# neopixel-6-display-controller.net
KiCad netlist of a schematic drawn in EasyEDA Pro
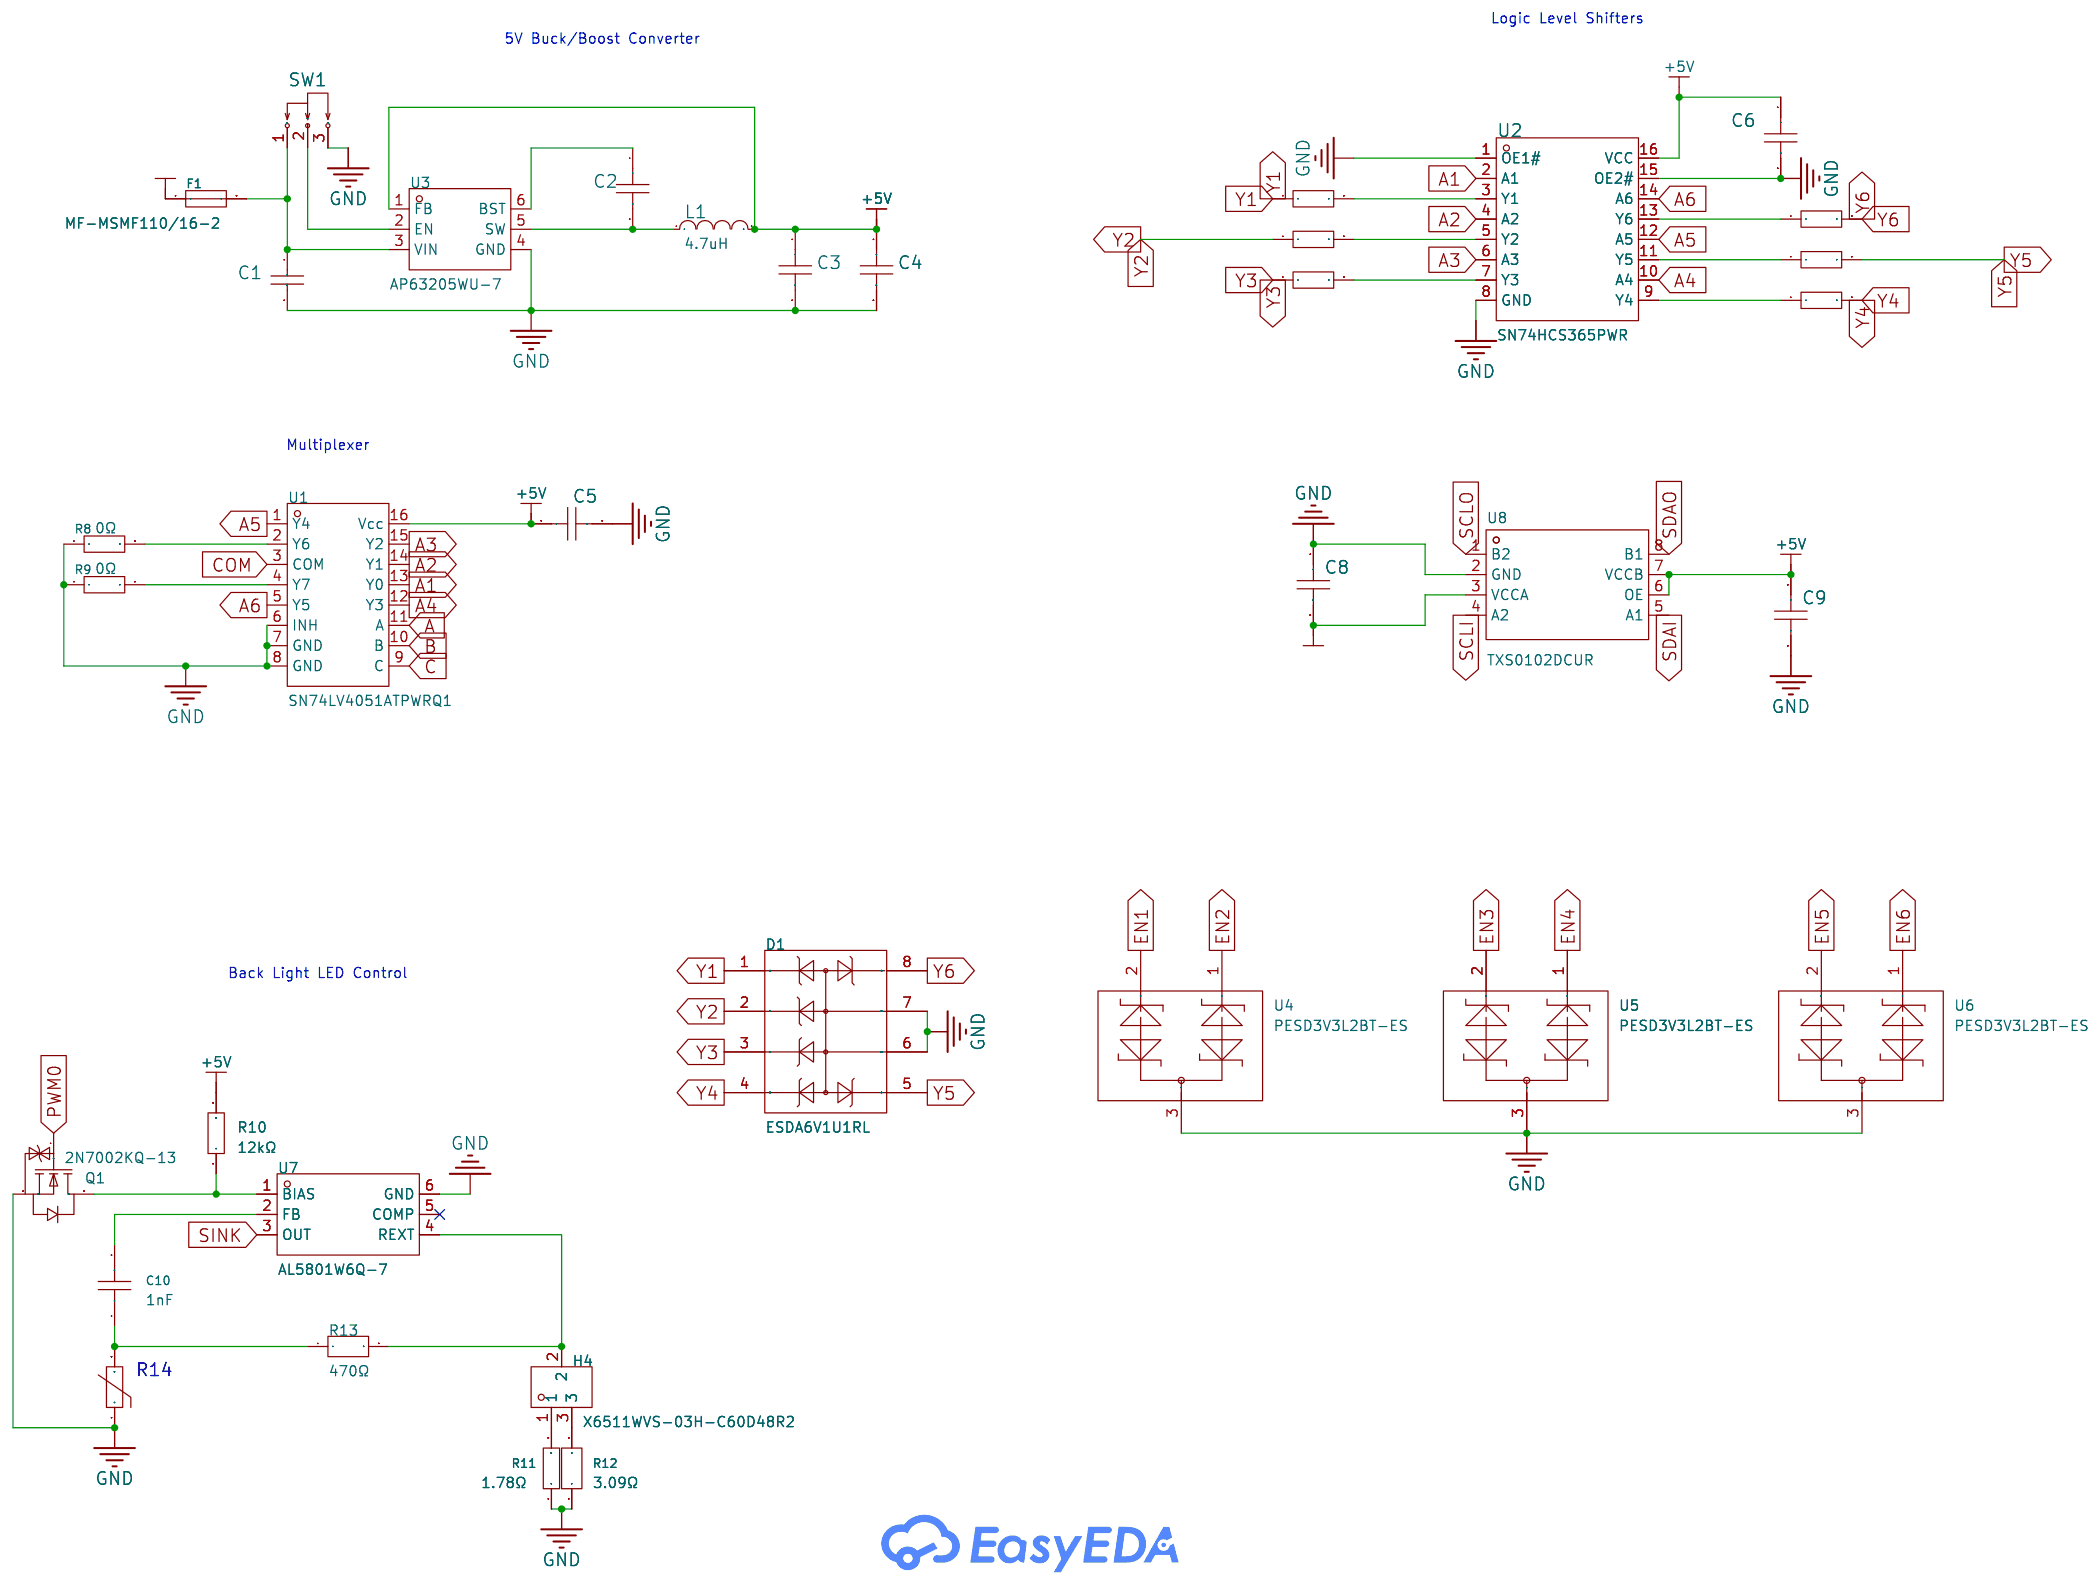
[diagram p0: Components]
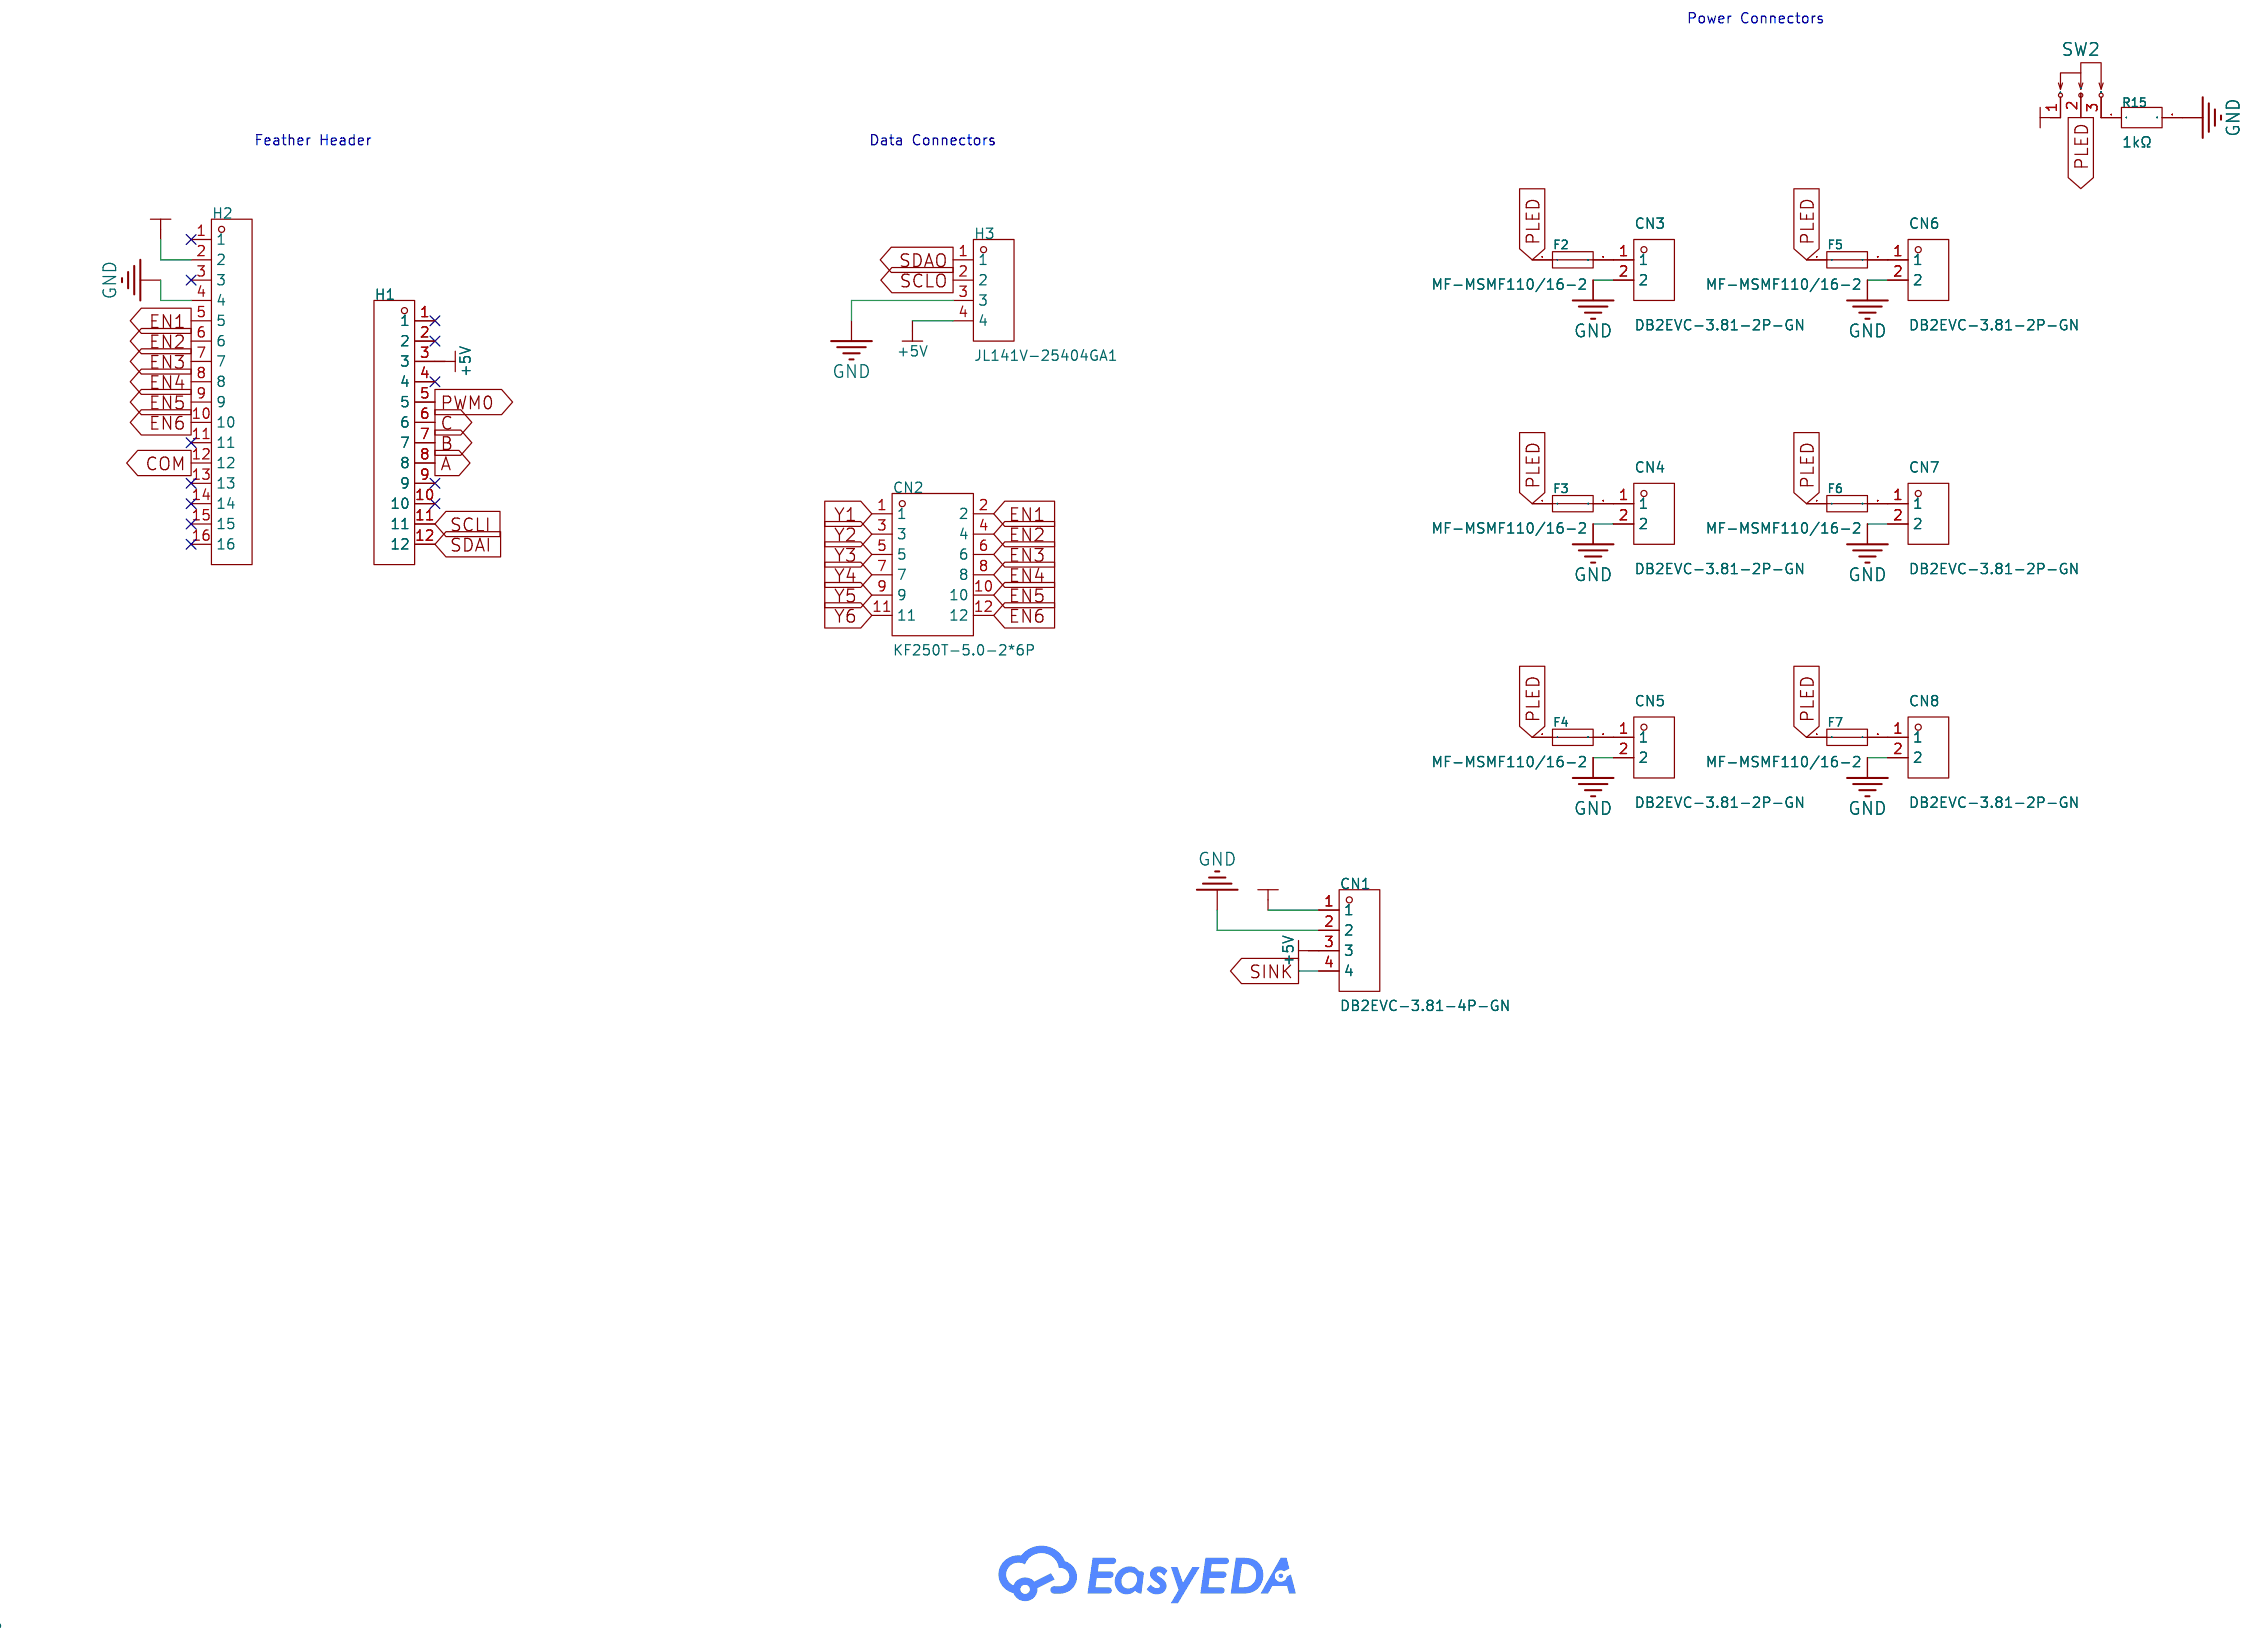
[diagram p1: Connectors]

(export (version "E")
  (design (tool "Eeschema 10.0.6"))
  (components
    (comp (ref "C1")
      (value "10uF")
      (footprint "easyedapro:C1210")
      (fields
        (field (name "Manufacturer Part") "CL32B106KAJNNNE")
        (field (name "Manufacturer") "SAMSUNG(三星)")
      )
      (libsource (lib "easyedapro") (part "CL32B106KAJNNNE"))
    )
    (comp (ref "C2")
      (value "100nF")
      (footprint "easyedapro:C1206")
      (fields (field (name "Manufacturer Part") "1206N104J500CT") (field (name "Manufacturer") "Walsin(华新科)"))
      (libsource (lib "easyedapro") (part "1206N104J500"))
    )
    (comp (ref "C3")
      (value "22uF")
      (footprint "easyedapro:C1210")
      (fields
        (field (name "Manufacturer Part") "CL32B226KAJNNNE")
        (field (name "Manufacturer") "SAMSUNG(三星)")
      )
      (libsource (lib "easyedapro") (part "CL32B226KAJNNNE"))
    )
    (comp (ref "C4")
      (value "22uF")
      (footprint "easyedapro:C1210")
      (fields
        (field (name "Manufacturer Part") "CL32B226KAJNNNE")
        (field (name "Manufacturer") "SAMSUNG(三星)")
      )
      (libsource (lib "easyedapro") (part "CL32B226KAJNNNE"))
    )
    (comp (ref "C5")
      (value "100nF")
      (footprint "easyedapro:C1206")
      (fields (field (name "Manufacturer Part") "1206N104J500CT") (field (name "Manufacturer") "Walsin(华新科)"))
      (libsource (lib "easyedapro") (part "1206N104J500"))
    )
    (comp (ref "C6")
      (value "100nF")
      (footprint "easyedapro:C1206")
      (fields (field (name "Manufacturer Part") "1206N104J500CT") (field (name "Manufacturer") "Walsin(华新科)"))
      (libsource (lib "easyedapro") (part "1206N104J500"))
    )
    (comp (ref "C8")
      (value "100nF")
      (footprint "easyedapro:C1206")
      (fields (field (name "Manufacturer Part") "1206N104J500CT") (field (name "Manufacturer") "Walsin(华新科)"))
      (libsource (lib "easyedapro") (part "1206N104J500"))
    )
    (comp (ref "C9")
      (value "100nF")
      (footprint "easyedapro:C1206")
      (fields (field (name "Manufacturer Part") "1206N104J500CT") (field (name "Manufacturer") "Walsin(华新科)"))
      (libsource (lib "easyedapro") (part "1206N104J500"))
    )
    (comp (ref "C10")
      (value "1nF")
      (footprint "easyedapro:C0402")
      (fields
        (field (name "Manufacturer Part") "GRM1555C1H102JA01D")
        (field (name "Manufacturer") "muRata(村田)")
      )
      (libsource (lib "easyedapro") (part "GRM1555C1H102JA01D"))
    )
    (comp (ref "D1")
      (value "ESDA6V1U1RL")
      (footprint "easyedapro:SO-8_L4.9-W3.9-P1.27-LS5.9-BL")
      (fields (field (name "Manufacturer") "ST(意法半导体)"))
      (libsource (lib "easyedapro") (part "ESDA6V1U1RL"))
    )
    (comp (ref "F1")
      (value "MF-MSMF110/16-2")
      (footprint "easyedapro:F1812")
      (fields (field (name "Manufacturer") "BOURNS"))
      (libsource (lib "easyedapro") (part "MF-MSMF110/16-2"))
    )
    (comp (ref "H4")
      (value "X6511WVS-03H-C60D48R2")
      (footprint "easyedapro:HDR-SMD_3P-P2.54_XKB_X6511WVS-03H-C60D48R2")
      (fields (field (name "Manufacturer") "XKB Connection(中国星坤)"))
      (libsource (lib "easyedapro") (part "X6511WVS-03H-C60D48R2"))
    )
    (comp (ref "L1")
      (value "4.7uH")
      (footprint "easyedapro:IND-SMD_L7.0-W7.0_CDRR7D45T125NP")
      (fields
        (field (name "Manufacturer Part") "CDRR7D45T125NP-4R7MC")
        (field (name "Manufacturer") "Sumida(胜美达)")
      )
      (libsource (lib "easyedapro") (part "CDRR7D45T125NP-4R7MC"))
    )
    (comp (ref "Q1")
      (value "2N7002KQ-13")
      (footprint "easyedapro:SOT-23-3_L2.9-W1.3-P1.90-LS2.4-BR")
      (fields (field (name "Manufacturer") "DIODES(美台)"))
      (libsource (lib "easyedapro") (part "2N7002KQ-13"))
    )
    (comp (ref "R1")
      (value "100Ω")
      (footprint "easyedapro:R0805")
      (fields (field (name "Manufacturer Part") "ERA6AEB101V") (field (name "Manufacturer") "PANASONIC(松下)"))
      (libsource (lib "easyedapro") (part "ERA6AEB101V"))
    )
    (comp (ref "R2")
      (value "100Ω")
      (footprint "easyedapro:R0805")
      (fields (field (name "Manufacturer Part") "ERA6AEB101V") (field (name "Manufacturer") "PANASONIC(松下)"))
      (libsource (lib "easyedapro") (part "ERA6AEB101V"))
    )
    (comp (ref "R3")
      (value "100Ω")
      (footprint "easyedapro:R0805")
      (fields (field (name "Manufacturer Part") "ERA6AEB101V") (field (name "Manufacturer") "PANASONIC(松下)"))
      (libsource (lib "easyedapro") (part "ERA6AEB101V"))
    )
    (comp (ref "R4")
      (value "100Ω")
      (footprint "easyedapro:R0805")
      (fields (field (name "Manufacturer Part") "ERA6AEB101V") (field (name "Manufacturer") "PANASONIC(松下)"))
      (libsource (lib "easyedapro") (part "ERA6AEB101V"))
    )
    (comp (ref "R5")
      (value "100Ω")
      (footprint "easyedapro:R0805")
      (fields (field (name "Manufacturer Part") "ERA6AEB101V") (field (name "Manufacturer") "PANASONIC(松下)"))
      (libsource (lib "easyedapro") (part "ERA6AEB101V"))
    )
    (comp (ref "R6")
      (value "100Ω")
      (footprint "easyedapro:R0805")
      (fields (field (name "Manufacturer Part") "ERA6AEB101V") (field (name "Manufacturer") "PANASONIC(松下)"))
      (libsource (lib "easyedapro") (part "ERA6AEB101V"))
    )
    (comp (ref "R8")
      (value "0Ω")
      (footprint "easyedapro:R0805")
      (fields (field (name "Manufacturer Part") "RTT050000FTP") (field (name "Manufacturer") "RALEC(旺诠)"))
      (libsource (lib "easyedapro") (part "RTT050000FTP"))
    )
    (comp (ref "R9")
      (value "0Ω")
      (footprint "easyedapro:R0805")
      (fields (field (name "Manufacturer Part") "RTT050000FTP") (field (name "Manufacturer") "RALEC(旺诠)"))
      (libsource (lib "easyedapro") (part "RTT050000FTP"))
    )
    (comp (ref "R10")
      (value "12kΩ")
      (footprint "easyedapro:R0805")
      (fields (field (name "Manufacturer Part") "PTFR0805B12K0N9") (field (name "Manufacturer") "RESI(开步睿思)"))
      (libsource (lib "easyedapro") (part "PTFR0805B12K0N9"))
    )
    (comp (ref "R11")
      (value "1.78Ω")
      (footprint "easyedapro:R0805")
      (fields
        (field (name "Manufacturer Part") "TR0805D1R78P0525")
        (field (name "Manufacturer") "EVER OHMS(天二科技)")
      )
      (libsource (lib "easyedapro") (part "TR0805D1R78P0525"))
    )
    (comp (ref "R12")
      (value "3.09Ω")
      (footprint "easyedapro:R0805")
      (fields (field (name "Manufacturer Part") "WR08W3R09FTL") (field (name "Manufacturer") "Walsin(华新科)"))
      (libsource (lib "easyedapro") (part "WR08W3R09FTL"))
    )
    (comp (ref "R13")
      (value "470Ω")
      (footprint "easyedapro:R0402")
      (fields (field (name "Manufacturer Part") "ERA2AEB471X") (field (name "Manufacturer") "PANASONIC(松下)"))
      (libsource (lib "easyedapro") (part "ERA2AEB471X"))
    )
    (comp (ref "R14")
      (value "10k")
      (footprint "easyedapro:R0805")
      (fields
        (field (name "Manufacturer Part") "KNTC0805/10KJ3450")
        (field (name "Manufacturer") "KUU")
        (field (name "Tolerance") "±0.5%")
      )
      (libsource (lib "easyedapro") (part "KNTC0805/10KJ3450"))
    )
    (comp (ref "SW1")
      (value "SS12D10G4 071")
      (footprint "easyedapro:SW-TH_SHOU-HAN_SS12D10G4")
      (fields (field (name "Manufacturer") "SHOU HAN(首韩)"))
      (libsource (lib "easyedapro") (part "SS12D10G4 071"))
    )
    (comp (ref "U1")
      (value "SN74LV4051ATPWRQ1")
      (footprint "easyedapro:TSSOP-16_L5.0-W4.4-P0.65-LS6.4-BL")
      (fields (field (name "Manufacturer") "TI(德州仪器)"))
      (libsource (lib "easyedapro") (part "SN74LV4051ATPWRQ1"))
    )
    (comp (ref "U2")
      (value "SN74HCS365PWR")
      (footprint "easyedapro:TSSOP-16_L5.0-W4.4-P0.65-LS6.4-BL")
      (fields (field (name "Manufacturer") "TI(德州仪器)"))
      (libsource (lib "easyedapro") (part "SN74HCS365PWR"))
    )
    (comp (ref "U3")
      (value "AP63205WU-7")
      (footprint "easyedapro:TSOT-23-6_L2.9-W1.6-P0.95-LS2.8-BL")
      (fields (field (name "Manufacturer") "DIODES(美台)"))
      (libsource (lib "easyedapro") (part "AP63205WU-7"))
    )
    (comp (ref "U4")
      (value "PESD3V3L2BT-ES")
      (footprint "easyedapro:SOT-23-3_L2.9-W1.3-P0.95-LS2.4-BR")
      (fields (field (name "Manufacturer") "ElecSuper(静芯微)"))
      (libsource (lib "easyedapro") (part "PESD3V3L2BT-ES"))
    )
    (comp (ref "U5")
      (value "PESD3V3L2BT-ES")
      (footprint "easyedapro:SOT-23-3_L2.9-W1.3-P0.95-LS2.4-BR")
      (fields (field (name "Manufacturer") "ElecSuper(静芯微)"))
      (libsource (lib "easyedapro") (part "PESD3V3L2BT-ES"))
    )
    (comp (ref "U6")
      (value "PESD3V3L2BT-ES")
      (footprint "easyedapro:SOT-23-3_L2.9-W1.3-P0.95-LS2.4-BR")
      (fields (field (name "Manufacturer") "ElecSuper(静芯微)"))
      (libsource (lib "easyedapro") (part "PESD3V3L2BT-ES"))
    )
    (comp (ref "U7")
      (value "AL5801W6Q-7")
      (footprint "easyedapro:SOT-26-6_L3.0-W1.6-P0.95-LS2.8-BL")
      (fields (field (name "Manufacturer") "DIODES(美台)"))
      (libsource (lib "easyedapro") (part "AL5801W6Q-7"))
    )
    (comp (ref "U8")
      (value "TXS0102DCUR")
      (footprint "easyedapro:VSON8_L2.0-W2.3-P0.50-LS3.1-BL")
      (fields (field (name "Manufacturer") "TI(德州仪器)"))
      (libsource (lib "easyedapro") (part "TXS0102DCUR"))
    )
    (comp (ref "CN1")
      (value "DB2EVC-3.81-4P-GN")
      (footprint "easyedapro:CONN-TH_4P-P3.81_DB2EVC-3.81-4P")
      (fields (field (name "Manufacturer") "DORABO(地博电气)"))
      (libsource (lib "easyedapro") (part "DB2EVC-3.81-4P"))
    )
    (comp (ref "CN2")
      (value "KF250T-5.0-2*6P")
      (footprint "easyedapro:CONN-TH_KF250T-5.0-2X6P")
      (fields (field (name "Manufacturer") "KEFA(科发)"))
      (libsource (lib "easyedapro") (part "KF250T-5.0-2*6P"))
    )
    (comp (ref "CN3")
      (value "DB2EVC-3.81-2P-GN")
      (footprint "easyedapro:CONN-TH_2P-P3.81_DB2EVC-3.81-2P-BK")
      (fields (field (name "Manufacturer") "DORABO(地博电气)"))
      (libsource (lib "easyedapro") (part "DB2EVC-3.81-2P"))
    )
    (comp (ref "CN4")
      (value "DB2EVC-3.81-2P-GN")
      (footprint "easyedapro:CONN-TH_2P-P3.81_DB2EVC-3.81-2P-BK")
      (fields (field (name "Manufacturer") "DORABO(地博电气)"))
      (libsource (lib "easyedapro") (part "DB2EVC-3.81-2P"))
    )
    (comp (ref "CN5")
      (value "DB2EVC-3.81-2P-GN")
      (footprint "easyedapro:CONN-TH_2P-P3.81_DB2EVC-3.81-2P-BK")
      (fields (field (name "Manufacturer") "DORABO(地博电气)"))
      (libsource (lib "easyedapro") (part "DB2EVC-3.81-2P"))
    )
    (comp (ref "CN6")
      (value "DB2EVC-3.81-2P-GN")
      (footprint "easyedapro:CONN-TH_2P-P3.81_DB2EVC-3.81-2P-BK")
      (fields (field (name "Manufacturer") "DORABO(地博电气)"))
      (libsource (lib "easyedapro") (part "DB2EVC-3.81-2P"))
    )
    (comp (ref "CN7")
      (value "DB2EVC-3.81-2P-GN")
      (footprint "easyedapro:CONN-TH_2P-P3.81_DB2EVC-3.81-2P-BK")
      (fields (field (name "Manufacturer") "DORABO(地博电气)"))
      (libsource (lib "easyedapro") (part "DB2EVC-3.81-2P"))
    )
    (comp (ref "CN8")
      (value "DB2EVC-3.81-2P-GN")
      (footprint "easyedapro:CONN-TH_2P-P3.81_DB2EVC-3.81-2P-BK")
      (fields (field (name "Manufacturer") "DORABO(地博电气)"))
      (libsource (lib "easyedapro") (part "DB2EVC-3.81-2P"))
    )
    (comp (ref "F2")
      (value "MF-MSMF110/16-2")
      (footprint "easyedapro:F1812")
      (fields (field (name "Manufacturer") "BOURNS"))
      (libsource (lib "easyedapro") (part "MF-MSMF110/16-2"))
    )
    (comp (ref "F3")
      (value "MF-MSMF110/16-2")
      (footprint "easyedapro:F1812")
      (fields (field (name "Manufacturer") "BOURNS"))
      (libsource (lib "easyedapro") (part "MF-MSMF110/16-2"))
    )
    (comp (ref "F4")
      (value "MF-MSMF110/16-2")
      (footprint "easyedapro:F1812")
      (fields (field (name "Manufacturer") "BOURNS"))
      (libsource (lib "easyedapro") (part "MF-MSMF110/16-2"))
    )
    (comp (ref "F5")
      (value "MF-MSMF110/16-2")
      (footprint "easyedapro:F1812")
      (fields (field (name "Manufacturer") "BOURNS"))
      (libsource (lib "easyedapro") (part "MF-MSMF110/16-2"))
    )
    (comp (ref "F6")
      (value "MF-MSMF110/16-2")
      (footprint "easyedapro:F1812")
      (fields (field (name "Manufacturer") "BOURNS"))
      (libsource (lib "easyedapro") (part "MF-MSMF110/16-2"))
    )
    (comp (ref "F7")
      (value "MF-MSMF110/16-2")
      (footprint "easyedapro:F1812")
      (fields (field (name "Manufacturer") "BOURNS"))
      (libsource (lib "easyedapro") (part "MF-MSMF110/16-2"))
    )
    (comp (ref "H1")
      (value "A2541HWV-12P")
      (footprint "easyedapro:HDR-TH_12P-P2.54-V-F")
      (fields (field (name "Manufacturer") "CJT(长江连接器)"))
      (libsource (lib "easyedapro") (part "PM2.54-1*12"))
    )
    (comp (ref "H2")
      (value "ZX-PM2.54-1-16PY")
      (footprint "easyedapro:HDR-TH_16P-P2.54-V-F-A")
      (fields (field (name "Manufacturer") "Megastar(兆星)"))
      (libsource (lib "easyedapro") (part "PM254-1-16-Z-8.5"))
    )
    (comp (ref "H3")
      (value "JL141V-25404GA1")
      (footprint "easyedapro:CONN-TH_4P-P2.54_JILN_JL141V-25404GA1")
      (fields (field (name "Manufacturer") "JILN(锦凌)"))
      (libsource (lib "easyedapro") (part "JL141V-25404GA1"))
    )
    (comp (ref "R15")
      (value "1kΩ")
      (footprint "easyedapro:R0805")
      (fields
        (field (name "Manufacturer Part") "ERJ-HP6F1001V")
        (field (name "Manufacturer") "PANASONIC(松下)")
      )
      (libsource (lib "easyedapro") (part "ERJ-HP6F1001V"))
    )
    (comp (ref "SW2")
      (value "SS12D10G4 071")
      (footprint "easyedapro:SW-TH_SHOU-HAN_SS12D10G4")
      (fields (field (name "Manufacturer") "SHOU HAN(首韩)"))
      (libsource (lib "easyedapro") (part "SS12D10G4 071"))
    )
  )
  (nets
    (net (code "1") (name "+3.3V") (class "Default")
      (node (ref "C8") (pin "2") (pinfunction "2_2") (pintype "unspecified"))
      (node (ref "H2") (pin "2") (pinfunction "2_2") (pintype "unspecified"))
      (node (ref "U8") (pin "3") (pinfunction "VCCA_3") (pintype "unspecified"))
    )
    (net (code "2") (name "+5V") (class "Default")
      (node (ref "C3") (pin "1") (pinfunction "1_1") (pintype "unspecified"))
      (node (ref "C4") (pin "1") (pinfunction "1_1") (pintype "unspecified"))
      (node (ref "C5") (pin "1") (pinfunction "1_1") (pintype "unspecified"))
      (node (ref "C6") (pin "1") (pinfunction "1_1") (pintype "unspecified"))
      (node (ref "C9") (pin "1") (pinfunction "1_1") (pintype "unspecified"))
      (node (ref "CN1") (pin "3") (pinfunction "3_3") (pintype "unspecified"))
      (node (ref "H1") (pin "3") (pinfunction "3_3") (pintype "unspecified"))
      (node (ref "H3") (pin "4") (pinfunction "4_4") (pintype "unspecified"))
      (node (ref "L1") (pin "2") (pinfunction "2_2") (pintype "input"))
      (node (ref "R10") (pin "2") (pinfunction "2_2") (pintype "unspecified"))
      (node (ref "U1") (pin "16") (pinfunction "Vcc_16") (pintype "unspecified"))
      (node (ref "U2") (pin "16") (pinfunction "VCC_16") (pintype "input"))
      (node (ref "U3") (pin "1") (pinfunction "FB_1") (pintype "input"))
      (node (ref "U8") (pin "6") (pinfunction "OE_6") (pintype "unspecified"))
      (node (ref "U8") (pin "7") (pinfunction "VCCB_7") (pintype "unspecified"))
    )
    (net (code "3") (name "A") (class "Default")
      (node (ref "H1") (pin "8") (pinfunction "8_8") (pintype "unspecified"))
      (node (ref "U1") (pin "11") (pinfunction "A_11") (pintype "unspecified"))
    )
    (net (code "4") (name "A1") (class "Default")
      (node (ref "U1") (pin "13") (pinfunction "Y0_13") (pintype "unspecified"))
      (node (ref "U2") (pin "2") (pinfunction "A1_2") (pintype "input"))
    )
    (net (code "5") (name "A2") (class "Default")
      (node (ref "U1") (pin "14") (pinfunction "Y1_14") (pintype "unspecified"))
      (node (ref "U2") (pin "4") (pinfunction "A2_4") (pintype "input"))
    )
    (net (code "6") (name "A3") (class "Default")
      (node (ref "U1") (pin "15") (pinfunction "Y2_15") (pintype "unspecified"))
      (node (ref "U2") (pin "6") (pinfunction "A3_6") (pintype "input"))
    )
    (net (code "7") (name "A4") (class "Default")
      (node (ref "U1") (pin "12") (pinfunction "Y3_12") (pintype "unspecified"))
      (node (ref "U2") (pin "10") (pinfunction "A4_10") (pintype "input"))
    )
    (net (code "8") (name "A5") (class "Default")
      (node (ref "U1") (pin "1") (pinfunction "Y4_1") (pintype "unspecified"))
      (node (ref "U2") (pin "12") (pinfunction "A5_12") (pintype "input"))
    )
    (net (code "9") (name "A6") (class "Default")
      (node (ref "U1") (pin "5") (pinfunction "Y5_5") (pintype "unspecified"))
      (node (ref "U2") (pin "14") (pinfunction "A6_14") (pintype "input"))
    )
    (net (code "10") (name "B") (class "Default")
      (node (ref "H1") (pin "7") (pinfunction "7_7") (pintype "unspecified"))
      (node (ref "U1") (pin "10") (pinfunction "B_10") (pintype "unspecified"))
    )
    (net (code "11") (name "C") (class "Default")
      (node (ref "H1") (pin "6") (pinfunction "6_6") (pintype "unspecified"))
      (node (ref "U1") (pin "9") (pinfunction "C_9") (pintype "unspecified"))
    )
    (net (code "12") (name "COM") (class "Default")
      (node (ref "H2") (pin "12") (pinfunction "12_12") (pintype "unspecified"))
      (node (ref "U1") (pin "3") (pinfunction "COM_3") (pintype "unspecified"))
    )
    (net (code "13") (name "EN1") (class "Default")
      (node (ref "CN2") (pin "2") (pinfunction "2_2") (pintype "unspecified"))
      (node (ref "H2") (pin "5") (pinfunction "5_5") (pintype "unspecified"))
      (node (ref "U4") (pin "2") (pinfunction "2_2") (pintype "input"))
    )
    (net (code "14") (name "EN2") (class "Default")
      (node (ref "CN2") (pin "4") (pinfunction "4_4") (pintype "unspecified"))
      (node (ref "H2") (pin "6") (pinfunction "6_6") (pintype "unspecified"))
      (node (ref "U4") (pin "1") (pinfunction "1_1") (pintype "input"))
    )
    (net (code "15") (name "EN3") (class "Default")
      (node (ref "CN2") (pin "6") (pinfunction "6_6") (pintype "unspecified"))
      (node (ref "H2") (pin "7") (pinfunction "7_7") (pintype "unspecified"))
      (node (ref "U5") (pin "2") (pinfunction "2_2") (pintype "input"))
    )
    (net (code "16") (name "EN4") (class "Default")
      (node (ref "CN2") (pin "8") (pinfunction "8_8") (pintype "unspecified"))
      (node (ref "H2") (pin "8") (pinfunction "8_8") (pintype "unspecified"))
      (node (ref "U5") (pin "1") (pinfunction "1_1") (pintype "input"))
    )
    (net (code "17") (name "EN5") (class "Default")
      (node (ref "CN2") (pin "10") (pinfunction "10_10") (pintype "unspecified"))
      (node (ref "H2") (pin "9") (pinfunction "9_9") (pintype "unspecified"))
      (node (ref "U6") (pin "2") (pinfunction "2_2") (pintype "input"))
    )
    (net (code "18") (name "EN6") (class "Default")
      (node (ref "CN2") (pin "12") (pinfunction "12_12") (pintype "unspecified"))
      (node (ref "H2") (pin "10") (pinfunction "10_10") (pintype "unspecified"))
      (node (ref "U6") (pin "1") (pinfunction "1_1") (pintype "input"))
    )
    (net (code "19") (name "GND") (class "Default")
      (node (ref "C1") (pin "2") (pinfunction "2_2") (pintype "input"))
      (node (ref "C3") (pin "2") (pinfunction "2_2") (pintype "unspecified"))
      (node (ref "C4") (pin "2") (pinfunction "2_2") (pintype "unspecified"))
      (node (ref "C5") (pin "2") (pinfunction "2_2") (pintype "unspecified"))
      (node (ref "C6") (pin "2") (pinfunction "2_2") (pintype "unspecified"))
      (node (ref "C8") (pin "1") (pinfunction "1_1") (pintype "unspecified"))
      (node (ref "C9") (pin "2") (pinfunction "2_2") (pintype "unspecified"))
      (node (ref "CN1") (pin "2") (pinfunction "2_2") (pintype "unspecified"))
      (node (ref "CN3") (pin "2") (pinfunction "2_2") (pintype "unspecified"))
      (node (ref "CN4") (pin "2") (pinfunction "2_2") (pintype "unspecified"))
      (node (ref "CN5") (pin "2") (pinfunction "2_2") (pintype "unspecified"))
      (node (ref "CN6") (pin "2") (pinfunction "2_2") (pintype "unspecified"))
      (node (ref "CN7") (pin "2") (pinfunction "2_2") (pintype "unspecified"))
      (node (ref "CN8") (pin "2") (pinfunction "2_2") (pintype "unspecified"))
      (node (ref "D1") (pin "6") (pinfunction "GND_6") (pintype "unspecified"))
      (node (ref "D1") (pin "7") (pinfunction "GND_7") (pintype "unspecified"))
      (node (ref "H2") (pin "4") (pinfunction "4_4") (pintype "unspecified"))
      (node (ref "H3") (pin "3") (pinfunction "3_3") (pintype "unspecified"))
      (node (ref "Q1") (pin "2") (pinfunction "S_2") (pintype "unspecified"))
      (node (ref "R11") (pin "1") (pinfunction "1_1") (pintype "input"))
      (node (ref "R12") (pin "1") (pinfunction "1_1") (pintype "input"))
      (node (ref "R14") (pin "1") (pinfunction "1_1") (pintype "unspecified"))
      (node (ref "R15") (pin "2") (pinfunction "2_2") (pintype "input"))
      (node (ref "R8") (pin "1") (pinfunction "1_1") (pintype "input"))
      (node (ref "R9") (pin "1") (pinfunction "1_1") (pintype "input"))
      (node (ref "SW1") (pin "3") (pinfunction "3_3") (pintype "input"))
      (node (ref "U1") (pin "6") (pinfunction "INH_6") (pintype "unspecified"))
      (node (ref "U1") (pin "7") (pinfunction "GND_7") (pintype "unspecified"))
      (node (ref "U1") (pin "8") (pinfunction "GND_8") (pintype "unspecified"))
      (node (ref "U2") (pin "1") (pinfunction "OE1#_1") (pintype "input"))
      (node (ref "U2") (pin "15") (pinfunction "OE2#_15") (pintype "input"))
      (node (ref "U2") (pin "8") (pinfunction "GND_8") (pintype "input"))
      (node (ref "U3") (pin "4") (pinfunction "GND_4") (pintype "input"))
      (node (ref "U4") (pin "3") (pinfunction "3_3") (pintype "input"))
      (node (ref "U5") (pin "3") (pinfunction "3_3") (pintype "input"))
      (node (ref "U6") (pin "3") (pinfunction "3_3") (pintype "input"))
      (node (ref "U7") (pin "6") (pinfunction "GND_6") (pintype "input"))
      (node (ref "U8") (pin "2") (pinfunction "GND_2") (pintype "unspecified"))
    )
    (net (code "20") (name "Net-(C10-Pad1)") (class "Default")
      (node (ref "C10") (pin "1") (pinfunction "1_1") (pintype "input"))
      (node (ref "R13") (pin "1") (pinfunction "1_1") (pintype "unspecified"))
      (node (ref "R14") (pin "2") (pinfunction "2_2") (pintype "unspecified"))
    )
    (net (code "21") (name "Net-(CN3-Pad1)") (class "Default")
      (node (ref "CN3") (pin "1") (pinfunction "1_1") (pintype "unspecified"))
      (node (ref "F2") (pin "2") (pinfunction "2_2") (pintype "input"))
    )
    (net (code "22") (name "Net-(CN4-Pad1)") (class "Default")
      (node (ref "CN4") (pin "1") (pinfunction "1_1") (pintype "unspecified"))
      (node (ref "F3") (pin "2") (pinfunction "2_2") (pintype "input"))
    )
    (net (code "23") (name "Net-(CN5-Pad1)") (class "Default")
      (node (ref "CN5") (pin "1") (pinfunction "1_1") (pintype "unspecified"))
      (node (ref "F4") (pin "2") (pinfunction "2_2") (pintype "input"))
    )
    (net (code "24") (name "Net-(CN6-Pad1)") (class "Default")
      (node (ref "CN6") (pin "1") (pinfunction "1_1") (pintype "unspecified"))
      (node (ref "F5") (pin "2") (pinfunction "2_2") (pintype "input"))
    )
    (net (code "25") (name "Net-(CN7-Pad1)") (class "Default")
      (node (ref "CN7") (pin "1") (pinfunction "1_1") (pintype "unspecified"))
      (node (ref "F6") (pin "2") (pinfunction "2_2") (pintype "input"))
    )
    (net (code "26") (name "Net-(CN8-Pad1)") (class "Default")
      (node (ref "CN8") (pin "1") (pinfunction "1_1") (pintype "unspecified"))
      (node (ref "F7") (pin "2") (pinfunction "2_2") (pintype "input"))
    )
    (net (code "27") (name "Net-(H4-Pad1)") (class "Default")
      (node (ref "H4") (pin "1") (pinfunction "1_1") (pintype "unspecified"))
      (node (ref "R11") (pin "2") (pinfunction "2_2") (pintype "input"))
    )
    (net (code "28") (name "Net-(H4-Pad3)") (class "Default")
      (node (ref "H4") (pin "3") (pinfunction "3_3") (pintype "unspecified"))
      (node (ref "R12") (pin "2") (pinfunction "2_2") (pintype "input"))
    )
    (net (code "29") (name "Net-(Q1-D)") (class "Default")
      (node (ref "Q1") (pin "3") (pinfunction "D_3") (pintype "unspecified"))
      (node (ref "R10") (pin "1") (pinfunction "1_1") (pintype "unspecified"))
      (node (ref "U7") (pin "1") (pinfunction "BIAS_1") (pintype "input"))
    )
    (net (code "30") (name "Net-(R15-Pad1)") (class "Default")
      (node (ref "R15") (pin "1") (pinfunction "1_1") (pintype "input"))
      (node (ref "SW2") (pin "3") (pinfunction "3_3") (pintype "input"))
    )
    (net (code "31") (name "Net-(U1-Y6)") (class "Default")
      (node (ref "R8") (pin "2") (pinfunction "2_2") (pintype "input"))
      (node (ref "U1") (pin "2") (pinfunction "Y6_2") (pintype "unspecified"))
    )
    (net (code "32") (name "Net-(U1-Y7)") (class "Default")
      (node (ref "R9") (pin "2") (pinfunction "2_2") (pintype "input"))
      (node (ref "U1") (pin "4") (pinfunction "Y7_4") (pintype "unspecified"))
    )
    (net (code "33") (name "Net-(U2-Y1)") (class "Default")
      (node (ref "R1") (pin "2") (pinfunction "2_2") (pintype "input"))
      (node (ref "U2") (pin "3") (pinfunction "Y1_3") (pintype "input"))
    )
    (net (code "34") (name "Net-(U2-Y2)") (class "Default")
      (node (ref "R2") (pin "2") (pinfunction "2_2") (pintype "input"))
      (node (ref "U2") (pin "5") (pinfunction "Y2_5") (pintype "input"))
    )
    (net (code "35") (name "Net-(U2-Y3)") (class "Default")
      (node (ref "R3") (pin "2") (pinfunction "2_2") (pintype "input"))
      (node (ref "U2") (pin "7") (pinfunction "Y3_7") (pintype "input"))
    )
    (net (code "36") (name "Net-(U2-Y4)") (class "Default")
      (node (ref "R4") (pin "1") (pinfunction "1_1") (pintype "input"))
      (node (ref "U2") (pin "9") (pinfunction "Y4_9") (pintype "input"))
    )
    (net (code "37") (name "Net-(U2-Y5)") (class "Default")
      (node (ref "R5") (pin "1") (pinfunction "1_1") (pintype "input"))
      (node (ref "U2") (pin "11") (pinfunction "Y5_11") (pintype "input"))
    )
    (net (code "38") (name "Net-(U2-Y6)") (class "Default")
      (node (ref "R6") (pin "1") (pinfunction "1_1") (pintype "input"))
      (node (ref "U2") (pin "13") (pinfunction "Y6_13") (pintype "input"))
    )
    (net (code "39") (name "Net-(U3-BST)") (class "Default")
      (node (ref "C2") (pin "1") (pinfunction "1_1") (pintype "unspecified"))
      (node (ref "U3") (pin "6") (pinfunction "BST_6") (pintype "input"))
    )
    (net (code "40") (name "Net-(U3-EN)") (class "Default")
      (node (ref "SW1") (pin "2") (pinfunction "2_2") (pintype "input"))
      (node (ref "U3") (pin "2") (pinfunction "EN_2") (pintype "input"))
    )
    (net (code "41") (name "Net-(U3-SW)") (class "Default")
      (node (ref "C2") (pin "2") (pinfunction "2_2") (pintype "unspecified"))
      (node (ref "L1") (pin "1") (pinfunction "1_1") (pintype "input"))
      (node (ref "U3") (pin "5") (pinfunction "SW_5") (pintype "input"))
    )
    (net (code "42") (name "Net-(U3-VIN)") (class "Default")
      (node (ref "C1") (pin "1") (pinfunction "1_1") (pintype "input"))
      (node (ref "F1") (pin "2") (pinfunction "2_2") (pintype "input"))
      (node (ref "SW1") (pin "1") (pinfunction "1_1") (pintype "input"))
      (node (ref "U3") (pin "3") (pinfunction "VIN_3") (pintype "input"))
    )
    (net (code "43") (name "Net-(U7-FB)") (class "Default")
      (node (ref "C10") (pin "2") (pinfunction "2_2") (pintype "input"))
      (node (ref "U7") (pin "2") (pinfunction "FB_2") (pintype "input"))
    )
    (net (code "44") (name "Net-(U7-REXT)") (class "Default")
      (node (ref "H4") (pin "2") (pinfunction "2_2") (pintype "unspecified"))
      (node (ref "R13") (pin "2") (pinfunction "2_2") (pintype "unspecified"))
      (node (ref "U7") (pin "4") (pinfunction "REXT_4") (pintype "input"))
    )
    (net (code "45") (name "PLED") (class "Default")
      (node (ref "F2") (pin "1") (pinfunction "1_1") (pintype "input"))
      (node (ref "F3") (pin "1") (pinfunction "1_1") (pintype "input"))
      (node (ref "F4") (pin "1") (pinfunction "1_1") (pintype "input"))
      (node (ref "F5") (pin "1") (pinfunction "1_1") (pintype "input"))
      (node (ref "F6") (pin "1") (pinfunction "1_1") (pintype "input"))
      (node (ref "F7") (pin "1") (pinfunction "1_1") (pintype "input"))
      (node (ref "SW2") (pin "2") (pinfunction "2_2") (pintype "input"))
    )
    (net (code "46") (name "PWM0") (class "Default")
      (node (ref "H1") (pin "5") (pinfunction "5_5") (pintype "unspecified"))
      (node (ref "Q1") (pin "1") (pinfunction "G_1") (pintype "unspecified"))
    )
    (net (code "47") (name "SCLI") (class "Default")
      (node (ref "H1") (pin "11") (pinfunction "11_11") (pintype "unspecified"))
      (node (ref "U8") (pin "4") (pinfunction "A2_4") (pintype "unspecified"))
    )
    (net (code "48") (name "SCLO") (class "Default")
      (node (ref "H3") (pin "2") (pinfunction "2_2") (pintype "unspecified"))
      (node (ref "U8") (pin "1") (pinfunction "B2_1") (pintype "unspecified"))
    )
    (net (code "49") (name "SDAI") (class "Default")
      (node (ref "H1") (pin "12") (pinfunction "12_12") (pintype "unspecified"))
      (node (ref "U8") (pin "5") (pinfunction "A1_5") (pintype "unspecified"))
    )
    (net (code "50") (name "SDAO") (class "Default")
      (node (ref "H3") (pin "1") (pinfunction "1_1") (pintype "unspecified"))
      (node (ref "U8") (pin "8") (pinfunction "B1_8") (pintype "unspecified"))
    )
    (net (code "51") (name "SINK") (class "Default")
      (node (ref "CN1") (pin "4") (pinfunction "4_4") (pintype "unspecified"))
      (node (ref "U7") (pin "3") (pinfunction "OUT_3") (pintype "input"))
    )
    (net (code "52") (name "VCC") (class "Default")
      (node (ref "CN1") (pin "1") (pinfunction "1_1") (pintype "unspecified"))
      (node (ref "F1") (pin "1") (pinfunction "1_1") (pintype "input"))
      (node (ref "SW2") (pin "1") (pinfunction "1_1") (pintype "input"))
    )
    (net (code "53") (name "Y1") (class "Default")
      (node (ref "CN2") (pin "1") (pinfunction "1_1") (pintype "unspecified"))
      (node (ref "D1") (pin "1") (pinfunction "I/O1_1") (pintype "unspecified"))
      (node (ref "R1") (pin "1") (pinfunction "1_1") (pintype "input"))
    )
    (net (code "54") (name "Y2") (class "Default")
      (node (ref "CN2") (pin "3") (pinfunction "3_3") (pintype "unspecified"))
      (node (ref "D1") (pin "2") (pinfunction "I/O2_2") (pintype "unspecified"))
      (node (ref "R2") (pin "1") (pinfunction "1_1") (pintype "input"))
    )
    (net (code "55") (name "Y3") (class "Default")
      (node (ref "CN2") (pin "5") (pinfunction "5_5") (pintype "unspecified"))
      (node (ref "D1") (pin "3") (pinfunction "I/O3_3") (pintype "unspecified"))
      (node (ref "R3") (pin "1") (pinfunction "1_1") (pintype "input"))
    )
    (net (code "56") (name "Y4") (class "Default")
      (node (ref "CN2") (pin "7") (pinfunction "7_7") (pintype "unspecified"))
      (node (ref "D1") (pin "4") (pinfunction "I/O4_4") (pintype "unspecified"))
      (node (ref "R4") (pin "2") (pinfunction "2_2") (pintype "input"))
    )
    (net (code "57") (name "Y5") (class "Default")
      (node (ref "CN2") (pin "9") (pinfunction "9_9") (pintype "unspecified"))
      (node (ref "D1") (pin "5") (pinfunction "I/O5_5") (pintype "unspecified"))
      (node (ref "R5") (pin "2") (pinfunction "2_2") (pintype "input"))
    )
    (net (code "58") (name "Y6") (class "Default")
      (node (ref "CN2") (pin "11") (pinfunction "11_11") (pintype "unspecified"))
      (node (ref "D1") (pin "8") (pinfunction "I/O6_8") (pintype "unspecified"))
      (node (ref "R6") (pin "2") (pinfunction "2_2") (pintype "input"))
    )
    (net (code "59") (name "unconnected-(H1-Pad1)") (class "Default")
      (node (ref "H1") (pin "1") (pinfunction "1_1") (pintype "unspecified+no_connect"))
    )
    (net (code "60") (name "unconnected-(H1-Pad2)") (class "Default")
      (node (ref "H1") (pin "2") (pinfunction "2_2") (pintype "unspecified+no_connect"))
    )
    (net (code "61") (name "unconnected-(H1-Pad4)") (class "Default")
      (node (ref "H1") (pin "4") (pinfunction "4_4") (pintype "unspecified+no_connect"))
    )
    (net (code "62") (name "unconnected-(H1-Pad9)") (class "Default")
      (node (ref "H1") (pin "9") (pinfunction "9_9") (pintype "unspecified+no_connect"))
    )
    (net (code "63") (name "unconnected-(H1-Pad10)") (class "Default")
      (node (ref "H1") (pin "10") (pinfunction "10_10") (pintype "unspecified+no_connect"))
    )
    (net (code "64") (name "unconnected-(H2-Pad1)") (class "Default")
      (node (ref "H2") (pin "1") (pinfunction "1_1") (pintype "unspecified+no_connect"))
    )
    (net (code "65") (name "unconnected-(H2-Pad3)") (class "Default")
      (node (ref "H2") (pin "3") (pinfunction "3_3") (pintype "unspecified+no_connect"))
    )
    (net (code "66") (name "unconnected-(H2-Pad11)") (class "Default")
      (node (ref "H2") (pin "11") (pinfunction "11_11") (pintype "unspecified+no_connect"))
    )
    (net (code "67") (name "unconnected-(H2-Pad13)") (class "Default")
      (node (ref "H2") (pin "13") (pinfunction "13_13") (pintype "unspecified+no_connect"))
    )
    (net (code "68") (name "unconnected-(H2-Pad14)") (class "Default")
      (node (ref "H2") (pin "14") (pinfunction "14_14") (pintype "unspecified+no_connect"))
    )
    (net (code "69") (name "unconnected-(H2-Pad15)") (class "Default")
      (node (ref "H2") (pin "15") (pinfunction "15_15") (pintype "unspecified+no_connect"))
    )
    (net (code "70") (name "unconnected-(H2-Pad16)") (class "Default")
      (node (ref "H2") (pin "16") (pinfunction "16_16") (pintype "unspecified+no_connect"))
    )
    (net (code "71") (name "unconnected-(U7-COMP-Pad5)") (class "Default")
      (node (ref "U7") (pin "5") (pinfunction "COMP_5") (pintype "input+no_connect"))
    )
  )
)
